# Mobile_adapter_5V_1A_LQ.net
KiCad netlist of a schematic drawn in Altium Designer
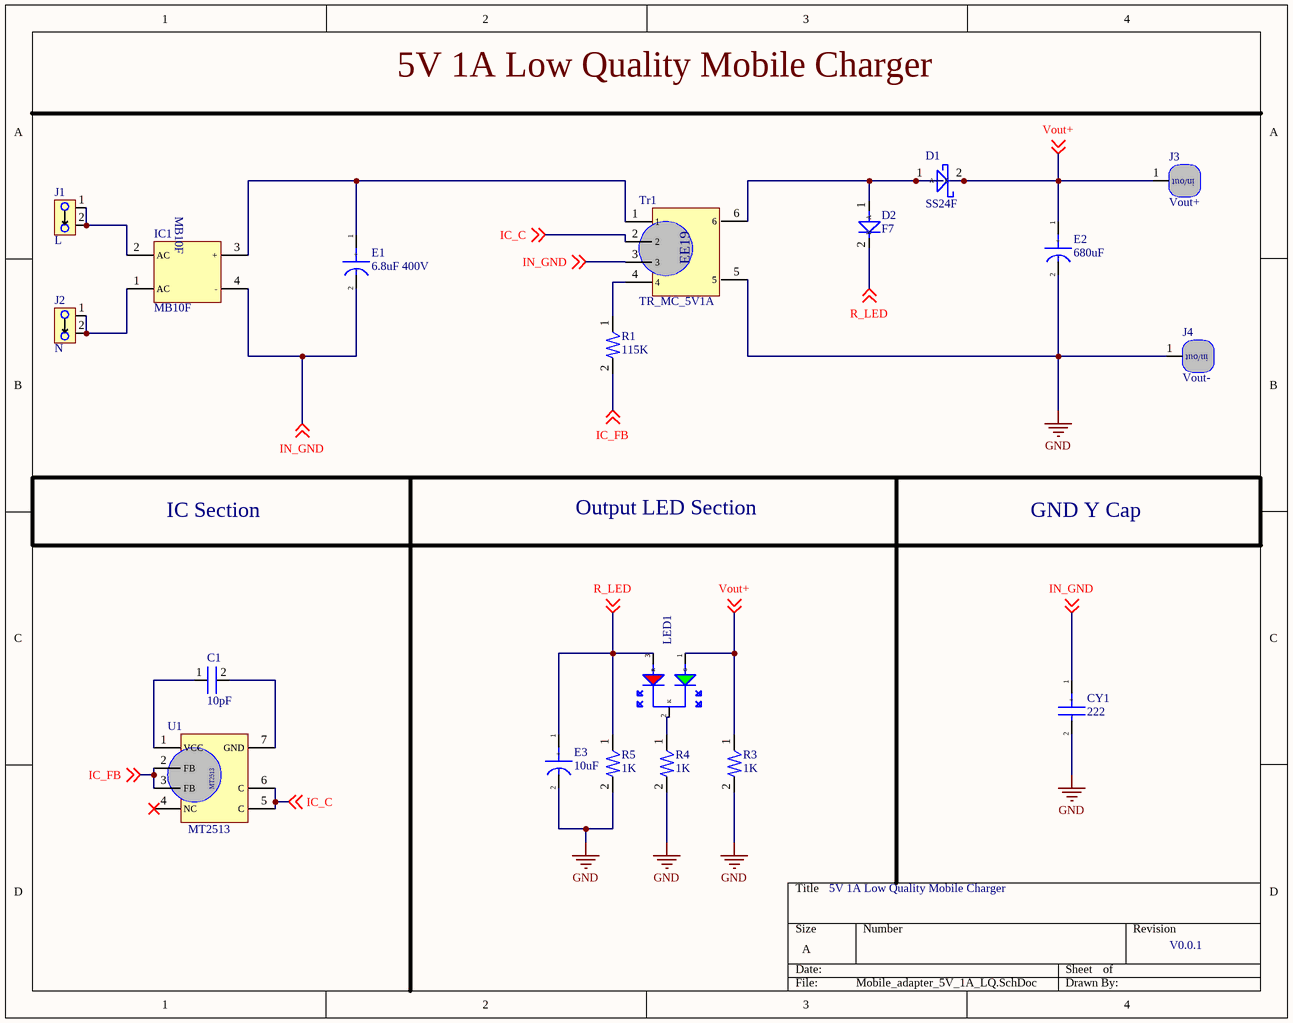
[diagram p0: Mobile_adapter_5V_1A_LQ.SchDoc]

(export (version "E")
  (design (tool "Eeschema 10.0.6"))
  (components
    (comp (ref "C1")
      (value "10pF")
      (footprint "C_0603")
      (description "25V 10pF C0G ±5% 0603 Multilayer Ceramic Capacitors MLCC - SMD/SMT ROHS")
      (libsource (lib "Custom pcb schamatic") (part "C_0603"))
    )
    (comp (ref "CY1")
      (value "222")
      (footprint "C_TH_104/102")
      (description "Keltron 222 1kv Capacitor")
      (libsource (lib "Custom pcb schamatic") (part "C_TH_104/102"))
    )
    (comp (ref "D1")
      (value "SS24F")
      (footprint "SMAF")
      (description "40V 550mV@2A 2A SMAF Schottky Diodes ROHS")
      (libsource (lib "Custom pcb schamatic") (part "D_SS24F_SK_SMAF"))
    )
    (comp (ref "D2")
      (value "F7")
      (footprint "SOD123F-F7")
      (description "1.3V@1A 500ns Independent Type 1A 1kV SOD-123F Fast Recovery / High Efficiency Diodes ROHS")
      (libsource (lib "Custom pcb schamatic") (part "D_F7_SOD123"))
    )
    (comp (ref "E1")
      (value "6.8uF 400V")
      (footprint "CAP_D8XL13")
      (description "6.8uF 400V ±20% Plugin,D8xL12mm Aluminum Electrolytic Capacitors - Leaded ROHS")
      (libsource (lib "Custom pcb schamatic") (part "C_D8XL13"))
    )
    (comp (ref "E2")
      (value "680uF")
      (footprint "CAP_D6.5XL12")
      (description "680uF 6.3V ±20% Plugin,D6.3xL12mm Aluminum Electrolytic Capacitors - Leaded ROHS")
      (libsource (lib "Custom pcb schamatic") (part "C_D6.5XL12"))
    )
    (comp (ref "E3")
      (value "10uF")
      (footprint "CAP_D5XL11")
      (description "10uF 50V ±20% Plugin,D5xL7mm Aluminum Electrolytic Capacitors - Leaded ROHS")
      (libsource (lib "Custom pcb schamatic") (part "C_D5XL11"))
    )
    (comp (ref "IC1")
      (value "MB10F")
      (footprint "MB10F")
      (description "30A 1.1V@800mA 800mA 1kV MBF Bridge Rectifiers ROHS")
      (libsource (lib "Custom pcb schamatic") (part "MB10F"))
    )
    (comp (ref "J1")
      (value "L")
      (footprint "MMT Metal shrapnel connector")
      (description "Metal Shrapnel mmt connector mobile charger")
      (libsource (lib "Custom pcb schamatic") (part "Metal Shrapnel mmt connector"))
    )
    (comp (ref "J2")
      (value "N")
      (footprint "MMT Metal shrapnel connector")
      (description "Metal Shrapnel mmt connector mobile charger")
      (libsource (lib "Custom pcb schamatic") (part "Metal Shrapnel mmt connector"))
    )
    (comp (ref "J3")
      (value "Vout+")
      (footprint "Wire solder connector _SMD - duplicate")
      (libsource (lib "Custom pcb schamatic") (part "Wire solder connector _SMD"))
    )
    (comp (ref "J4")
      (value "Vout-")
      (footprint "Wire solder connector _SMD - duplicate")
      (libsource (lib "Custom pcb schamatic") (part "Wire solder connector _SMD"))
    )
    (comp (ref "LED1")
      (value "LED 3mm RG Com cathod")
      (footprint "LED_RG_3mm")
      (description "Red Green Common Cathode  P=2.54mm")
      (libsource (lib "Custom pcb schamatic") (part "LED 3mm RG Com cathod"))
    )
    (comp (ref "R1")
      (value "115K")
      (footprint "R_0603")
      (description "100mW Thin Film Resistor ±50ppm/℃ ±0.1% 115kΩ 0603 Chip Resistor - Surface Mount ROHS")
      (libsource (lib "Custom pcb schamatic") (part "R_0603"))
    )
    (comp (ref "R3")
      (value "1K")
      (footprint "R_0603")
      (description "100mW Thick Film Resistors 75V ±100ppm/℃ ±1% 1kΩ 0603 Chip Resistor - Surface Mount ROHS")
      (libsource (lib "Custom pcb schamatic") (part "R_0603"))
    )
    (comp (ref "R4")
      (value "1K")
      (footprint "R_0603")
      (description "100mW Thick Film Resistors 75V ±100ppm/℃ ±1% 1kΩ 0603 Chip Resistor - Surface Mount ROHS")
      (libsource (lib "Custom pcb schamatic") (part "R_0603"))
    )
    (comp (ref "R5")
      (value "1K")
      (footprint "R_0603")
      (description "100mW Thick Film Resistors 75V ±100ppm/℃ ±1% 1kΩ 0603 Chip Resistor - Surface Mount ROHS")
      (libsource (lib "Custom pcb schamatic") (part "R_0603"))
    )
    (comp (ref "Tr1")
      (value "TR_MC_5V1A")
      (footprint "T_EE19_5V1A")
      (libsource (lib "Custom pcb schamatic") (part "T_EE19_5V1A"))
    )
    (comp (ref "U1")
      (value "MT2513")
      (footprint "SOP8-7")
      (description "MT2513 SOP8 Integrated Circuits")
      (libsource (lib "Custom pcb schamatic") (part "MT2513"))
    )
  )
  (nets
    (net (code "1") (name "GND") (class "Default")
      (node (ref "CY1") (pin "2") (pinfunction "-_2") (pintype "passive"))
      (node (ref "E2") (pin "2") (pinfunction "-_2") (pintype "passive"))
      (node (ref "E3") (pin "2") (pinfunction "-_2") (pintype "passive"))
      (node (ref "J4") (pin "1") (pinfunction "1_1") (pintype "passive"))
      (node (ref "R3") (pin "2") (pinfunction "2_2") (pintype "passive"))
      (node (ref "R4") (pin "2") (pinfunction "2_2") (pintype "passive"))
      (node (ref "R5") (pin "2") (pinfunction "2_2") (pintype "passive"))
      (node (ref "Tr1") (pin "5") (pinfunction "5_5") (pintype "passive"))
    )
    (net (code "2") (name "IC_C") (class "Default")
      (node (ref "Tr1") (pin "2") (pinfunction "2_2") (pintype "passive"))
      (node (ref "U1") (pin "5") (pinfunction "C_5") (pintype "passive"))
      (node (ref "U1") (pin "6") (pinfunction "C_6") (pintype "passive"))
    )
    (net (code "3") (name "IC_FB") (class "Default")
      (node (ref "R1") (pin "2") (pinfunction "2_2") (pintype "passive"))
      (node (ref "U1") (pin "2") (pinfunction "FB_2") (pintype "passive"))
      (node (ref "U1") (pin "3") (pinfunction "FB_3") (pintype "passive"))
    )
    (net (code "4") (name "IN_GND") (class "Default")
      (node (ref "CY1") (pin "1") (pinfunction "+_1") (pintype "passive"))
      (node (ref "E1") (pin "2") (pinfunction "-_2") (pintype "passive"))
      (node (ref "IC1") (pin "4") (pinfunction "-_4") (pintype "passive"))
      (node (ref "Tr1") (pin "3") (pinfunction "3_3") (pintype "passive"))
    )
    (net (code "5") (name "Net-(D1-A)") (class "Default")
      (node (ref "D1") (pin "1") (pinfunction "A_1") (pintype "passive"))
      (node (ref "D2") (pin "1") (pinfunction "A_1") (pintype "passive"))
      (node (ref "Tr1") (pin "6") (pinfunction "6_6") (pintype "passive"))
    )
    (net (code "6") (name "Net-(E1-+)") (class "Default")
      (node (ref "E1") (pin "1") (pinfunction "+_1") (pintype "passive"))
      (node (ref "IC1") (pin "3") (pinfunction "+_3") (pintype "passive"))
      (node (ref "Tr1") (pin "1") (pinfunction "1_1") (pintype "passive"))
    )
    (net (code "7") (name "Net-(IC1-AC-Pad1)") (class "Default")
      (node (ref "IC1") (pin "1") (pinfunction "AC_1") (pintype "passive"))
      (node (ref "J2") (pin "1") (pinfunction "1_1") (pintype "passive"))
      (node (ref "J2") (pin "2") (pinfunction "2_2") (pintype "passive"))
    )
    (net (code "8") (name "Net-(IC1-AC-Pad2)") (class "Default")
      (node (ref "IC1") (pin "2") (pinfunction "AC_2") (pintype "passive"))
      (node (ref "J1") (pin "1") (pinfunction "1_1") (pintype "passive"))
      (node (ref "J1") (pin "2") (pinfunction "2_2") (pintype "passive"))
    )
    (net (code "9") (name "Net-(LED1-K)") (class "Default")
      (node (ref "LED1") (pin "2") (pinfunction "K_2") (pintype "passive"))
      (node (ref "R4") (pin "1") (pinfunction "1_1") (pintype "passive"))
    )
    (net (code "10") (name "Net-(R1-Pad1)") (class "Default")
      (node (ref "R1") (pin "1") (pinfunction "1_1") (pintype "passive"))
      (node (ref "Tr1") (pin "4") (pinfunction "4_4") (pintype "passive"))
    )
    (net (code "11") (name "Net-(U1-GND)") (class "Default")
      (node (ref "C1") (pin "2") (pinfunction "2_2") (pintype "passive"))
      (node (ref "U1") (pin "7") (pinfunction "GND_7") (pintype "passive"))
    )
    (net (code "12") (name "Net-(U1-VCC)") (class "Default")
      (node (ref "C1") (pin "1") (pinfunction "1_1") (pintype "passive"))
      (node (ref "U1") (pin "1") (pinfunction "VCC_1") (pintype "passive"))
    )
    (net (code "13") (name "R_LED") (class "Default")
      (node (ref "D2") (pin "2") (pinfunction "K_2") (pintype "passive"))
      (node (ref "E3") (pin "1") (pinfunction "+_1") (pintype "passive"))
      (node (ref "LED1") (pin "3") (pinfunction "R_3") (pintype "passive"))
      (node (ref "R5") (pin "1") (pinfunction "1_1") (pintype "passive"))
    )
    (net (code "14") (name "Vout+") (class "Default")
      (node (ref "D1") (pin "2") (pinfunction "K_2") (pintype "passive"))
      (node (ref "E2") (pin "1") (pinfunction "+_1") (pintype "passive"))
      (node (ref "J3") (pin "1") (pinfunction "1_1") (pintype "passive"))
      (node (ref "LED1") (pin "1") (pinfunction "G_1") (pintype "passive"))
      (node (ref "R3") (pin "1") (pinfunction "1_1") (pintype "passive"))
    )
    (net (code "15") (name "unconnected-(U1-NC-Pad4)") (class "Default")
      (node (ref "U1") (pin "4") (pinfunction "NC_4") (pintype "passive+no_connect"))
    )
  )
)
